# ESP32_Sensor.net
KiCad netlist of a schematic drawn in EAGLE
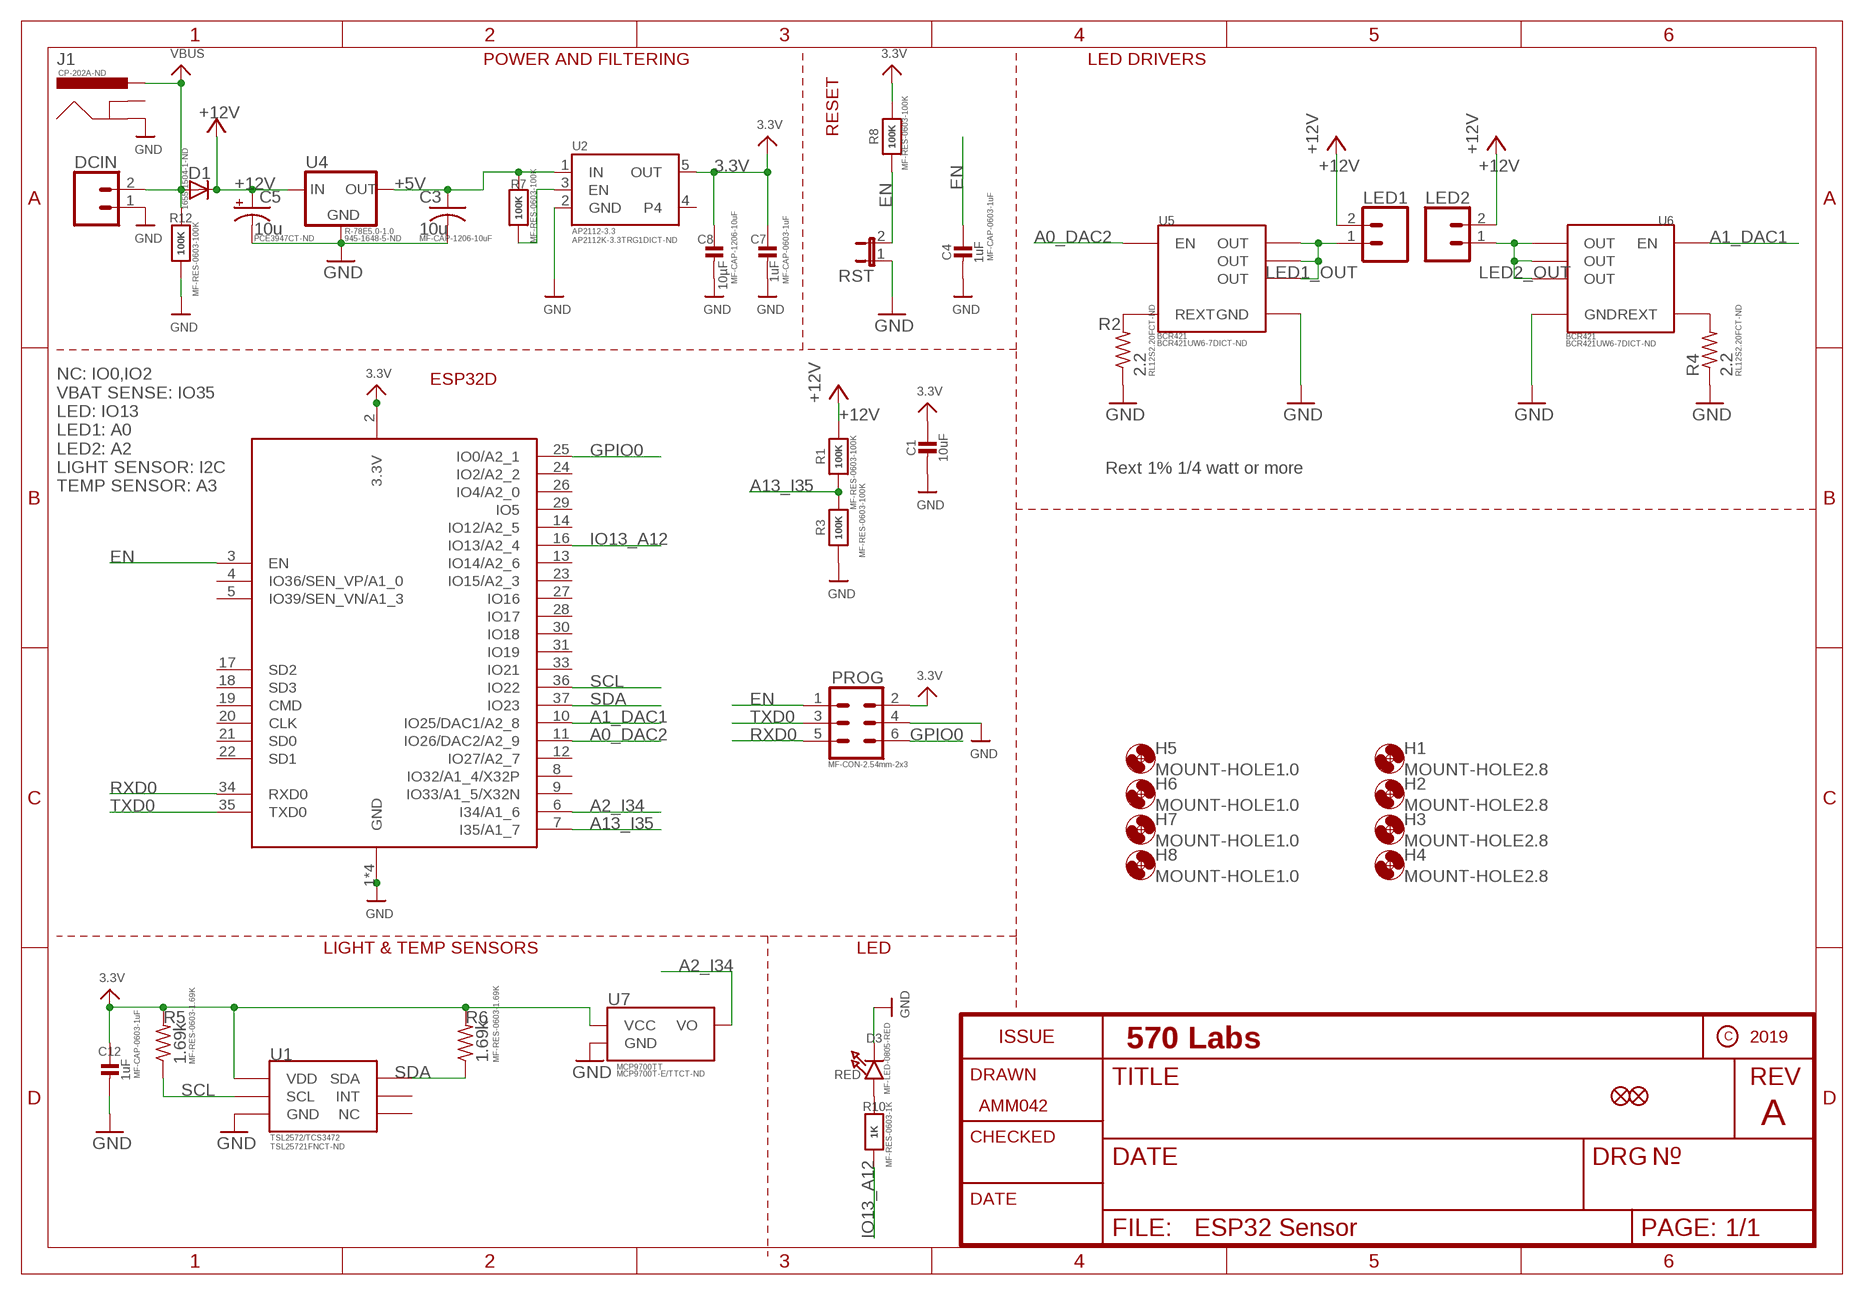
[diagram p0: schematic, sheet 1]

(export (version "E")
  (design (tool "Eeschema 10.0.6"))
  (components
    (comp (ref "C1")
      (value "10uF")
      (footprint "eagle-import:0805-NO")
      (libsource (lib "eagle-import") (part "CAP_CERAMIC0805-NOOUTLINE"))
    )
    (comp (ref "C3")
      (value "10u")
      (footprint "eagle-import:C1206")
      (fields (field (name "MF") "MF-CAP-1206-10uF"))
      (libsource (lib "eagle-import") (part "C-USC1206"))
    )
    (comp (ref "C4")
      (value "1uF")
      (footprint "eagle-import:0603-NO")
      (fields (field (name "MF") "MF-CAP-0603-1uF"))
      (libsource (lib "eagle-import") (part "CAP_CERAMIC0603_NO"))
    )
    (comp (ref "C5")
      (value "10u")
      (footprint "eagle-import:PANASONIC_C")
      (fields (field (name "DK") "PCE3947CT-ND"))
      (libsource (lib "eagle-import") (part "CPOL-USC"))
    )
    (comp (ref "C7")
      (value "1uF")
      (footprint "eagle-import:0603-NO")
      (fields (field (name "MF") "MF-CAP-0603-1uF"))
      (libsource (lib "eagle-import") (part "CAP_CERAMIC0603_NO"))
    )
    (comp (ref "C8")
      (value "10µF")
      (footprint "eagle-import:_1206")
      (fields (field (name "MF") "MF-CAP-1206-10uF"))
      (libsource (lib "eagle-import") (part "CAP_CERAMIC_1206"))
    )
    (comp (ref "C12")
      (value "1uF")
      (footprint "eagle-import:0603-NO")
      (fields (field (name "MF") "MF-CAP-0603-1uF"))
      (libsource (lib "eagle-import") (part "CAP_CERAMIC0603_NO"))
    )
    (comp (ref "D1")
      (value "DIODE-DO214AC")
      (footprint "eagle-import:DO214AC")
      (fields (field (name "DK") "1655-1504-1-ND"))
      (libsource (lib "eagle-import") (part "DIODE-DO214AC"))
    )
    (comp (ref "D3")
      (value "RED")
      (footprint "eagle-import:CHIPLED_0805_NOOUTLINE")
      (fields (field (name "MF") "MF-LED-0805-RED"))
      (libsource (lib "eagle-import") (part "LED0805_NOOUTLINE"))
    )
    (comp (ref "DCIN")
      (value "CONN_023.5MM")
      (footprint "eagle-import:SCREWTERMINAL-3.5MM-2")
      (libsource (lib "eagle-import") (part "CONN_023.5MM"))
    )
    (comp (ref "H1")
      (value "MOUNT-HOLE2.8")
      (footprint "eagle-import:2,8")
      (libsource (lib "eagle-import") (part "holes_237_MOUNT-HOLE2.8"))
    )
    (comp (ref "H2")
      (value "MOUNT-HOLE2.8")
      (footprint "eagle-import:2,8")
      (libsource (lib "eagle-import") (part "holes_237_MOUNT-HOLE2.8"))
    )
    (comp (ref "H3")
      (value "MOUNT-HOLE2.8")
      (footprint "eagle-import:2,8")
      (libsource (lib "eagle-import") (part "holes_237_MOUNT-HOLE2.8"))
    )
    (comp (ref "H4")
      (value "MOUNT-HOLE2.8")
      (footprint "eagle-import:2,8")
      (libsource (lib "eagle-import") (part "holes_237_MOUNT-HOLE2.8"))
    )
    (comp (ref "H5")
      (value "MOUNT-HOLE1.0")
      (footprint "eagle-import:1,0")
      (libsource (lib "eagle-import") (part "MOUNT-HOLE1.0"))
    )
    (comp (ref "H6")
      (value "MOUNT-HOLE1.0")
      (footprint "eagle-import:1,0")
      (libsource (lib "eagle-import") (part "MOUNT-HOLE1.0"))
    )
    (comp (ref "H7")
      (value "MOUNT-HOLE1.0")
      (footprint "eagle-import:1,0")
      (libsource (lib "eagle-import") (part "MOUNT-HOLE1.0"))
    )
    (comp (ref "H8")
      (value "MOUNT-HOLE1.0")
      (footprint "eagle-import:1,0")
      (libsource (lib "eagle-import") (part "MOUNT-HOLE1.0"))
    )
    (comp (ref "J1")
      (value "POWER_JACKPTH_LOCK")
      (footprint "eagle-import:POWER_JACK_PTH_LOCK")
      (libsource (lib "eagle-import") (part "POWER_JACKPTH_LOCK"))
    )
    (comp (ref "LED1")
      (value "CONN_023.5MM")
      (footprint "eagle-import:SCREWTERMINAL-3.5MM-2")
      (libsource (lib "eagle-import") (part "CONN_023.5MM"))
    )
    (comp (ref "LED2")
      (value "CONN_023.5MM")
      (footprint "eagle-import:SCREWTERMINAL-3.5MM-2")
      (libsource (lib "eagle-import") (part "CONN_023.5MM"))
    )
    (comp (ref "PROG")
      (value "CONN_03X2SHROUD")
      (footprint "eagle-import:2X3-SHROUDED")
      (fields (field (name "MF") "MF-CON-2.54mm-2x3"))
      (libsource (lib "eagle-import") (part "CONN_03X2SHROUD"))
    )
    (comp (ref "R1")
      (value "100K")
      (footprint "eagle-import:0603-NO")
      (fields (field (name "MF") "MF-RES-0603-100K"))
      (libsource (lib "eagle-import") (part "RESISTOR_0603_NOOUT"))
    )
    (comp (ref "R2")
      (value "2.2")
      (footprint "eagle-import:R0603")
      (fields (field (name "DK") "RL12S2.20FCT-ND"))
      (libsource (lib "eagle-import") (part "R-US_R0603"))
    )
    (comp (ref "R3")
      (value "100K")
      (footprint "eagle-import:0603-NO")
      (fields (field (name "MF") "MF-RES-0603-100K"))
      (libsource (lib "eagle-import") (part "RESISTOR_0603_NOOUT"))
    )
    (comp (ref "R4")
      (value "2.2")
      (footprint "eagle-import:R0603")
      (fields (field (name "DK") "RL12S2.20FCT-ND"))
      (libsource (lib "eagle-import") (part "R-US_R0603"))
    )
    (comp (ref "R5")
      (value "1.69k")
      (footprint "eagle-import:R0603")
      (fields (field (name "MF") "MF-RES-0603-1.69K"))
      (libsource (lib "eagle-import") (part "R-US_R0603"))
    )
    (comp (ref "R6")
      (value "1.69k")
      (footprint "eagle-import:R0603")
      (fields (field (name "MF") "MF-RES-0603-1.69K"))
      (libsource (lib "eagle-import") (part "R-US_R0603"))
    )
    (comp (ref "R7")
      (value "100K")
      (footprint "eagle-import:0603-NO")
      (fields (field (name "MF") "MF-RES-0603-100K"))
      (libsource (lib "eagle-import") (part "RESISTOR_0603_NOOUT"))
    )
    (comp (ref "R8")
      (value "100K")
      (footprint "eagle-import:0603-NO")
      (fields (field (name "MF") "MF-RES-0603-100K"))
      (libsource (lib "eagle-import") (part "RESISTOR_0603_NOOUT"))
    )
    (comp (ref "R10")
      (value "1K")
      (footprint "eagle-import:0603-NO")
      (fields (field (name "MF") "MF-RES-0603-1K"))
      (libsource (lib "eagle-import") (part "RESISTOR_0603_NOOUT"))
    )
    (comp (ref "R12")
      (value "100K")
      (footprint "eagle-import:0603-NO")
      (fields (field (name "MF") "MF-RES-0603-100K"))
      (libsource (lib "eagle-import") (part "RESISTOR_0603_NOOUT"))
    )
    (comp (ref "RST")
      (value "JP1E")
      (footprint "eagle-import:JP1")
      (libsource (lib "eagle-import") (part "JP1E"))
    )
    (comp (ref "U$34")
      (value "FIDUCIAL_1MM")
      (footprint "eagle-import:FIDUCIAL_1MM")
      (libsource (lib "eagle-import") (part "FIDUCIAL_1MM"))
    )
    (comp (ref "U$35")
      (value "FIDUCIAL_1MM")
      (footprint "eagle-import:FIDUCIAL_1MM")
      (libsource (lib "eagle-import") (part "FIDUCIAL_1MM"))
    )
    (comp (ref "U1")
      (value "TSL2572/TCS3472")
      (footprint "eagle-import:AMS_FN_6")
      (fields (field (name "DK") "TSL25721FNCT-ND"))
      (libsource (lib "eagle-import") (part "AMS_6FN_SENSOR"))
    )
    (comp (ref "U2")
      (value "AP2112-3.3")
      (footprint "eagle-import:SOT23-5")
      (fields (field (name "DK") "AP2112K-3.3TRG1DICT-ND"))
      (libsource (lib "eagle-import") (part "VREG_SOT23-5"))
    )
    (comp (ref "U3")
      (value "ESP32_WROOM32_SKINNY")
      (footprint "eagle-import:WROOM32_SKINNY")
      (libsource (lib "eagle-import") (part "ESP32_WROOM32_SKINNY"))
    )
    (comp (ref "U4")
      (value "R-78E5.0-1.0")
      (footprint "eagle-import:DC-DC_CONVERTER_78XX")
      (fields (field (name "DK") "945-1648-5-ND"))
      (libsource (lib "eagle-import") (part "R-78E5.0-1.0"))
    )
    (comp (ref "U5")
      (value "BCR421")
      (footprint "eagle-import:SOT26")
      (fields (field (name "DK") "BCR421UW6-7DICT-ND"))
      (libsource (lib "eagle-import") (part "BCR421"))
    )
    (comp (ref "U6")
      (value "BCR421")
      (footprint "eagle-import:SOT26")
      (fields (field (name "DK") "BCR421UW6-7DICT-ND"))
      (libsource (lib "eagle-import") (part "BCR421"))
    )
    (comp (ref "U7")
      (value "MCP9700TT")
      (footprint "eagle-import:SOT23-3")
      (fields (field (name "DK") "MCP9700T-E/TTCT-ND"))
      (libsource (lib "eagle-import") (part "MCP9700TT"))
    )
  )
  (nets
    (net (code "1") (name "+12V") (class "Default")
      (node (ref "C5") (pin "+") (pinfunction "+_+") (pintype "passive"))
      (node (ref "D1") (pin "C") (pinfunction "C_C") (pintype "passive"))
      (node (ref "LED1") (pin "2") (pinfunction "2_2") (pintype "passive"))
      (node (ref "LED2") (pin "2") (pinfunction "2_2") (pintype "passive"))
      (node (ref "R1") (pin "2") (pinfunction "2_2") (pintype "passive"))
      (node (ref "U4") (pin "VIN") (pinfunction "IN_VIN") (pintype "input"))
    )
    (net (code "2") (name "/+5V") (class "Default")
      (node (ref "C3") (pin "1") (pinfunction "1_1") (pintype "passive"))
      (node (ref "R7") (pin "2") (pinfunction "2_2") (pintype "passive"))
      (node (ref "U2") (pin "1") (pinfunction "IN_1") (pintype "power_in"))
      (node (ref "U4") (pin "VOUT") (pinfunction "OUT_VOUT") (pintype "passive"))
    )
    (net (code "3") (name "/A0_DAC2") (class "Default")
      (node (ref "U3") (pin "11") (pinfunction "IO26/DAC2/A2_9_11") (pintype "bidirectional"))
      (node (ref "U5") (pin "1") (pinfunction "EN_1") (pintype "bidirectional"))
    )
    (net (code "4") (name "/A1_DAC1") (class "Default")
      (node (ref "U3") (pin "10") (pinfunction "IO25/DAC1/A2_8_10") (pintype "bidirectional"))
      (node (ref "U6") (pin "1") (pinfunction "EN_1") (pintype "bidirectional"))
    )
    (net (code "5") (name "/A2_I34") (class "Default")
      (node (ref "U3") (pin "6") (pinfunction "I34/A1_6_6") (pintype "bidirectional"))
      (node (ref "U7") (pin "2") (pinfunction "VO_2") (pintype "bidirectional"))
    )
    (net (code "6") (name "/A13_I35") (class "Default")
      (node (ref "R1") (pin "1") (pinfunction "1_1") (pintype "passive"))
      (node (ref "R3") (pin "2") (pinfunction "2_2") (pintype "passive"))
      (node (ref "U3") (pin "7") (pinfunction "I35/A1_7_7") (pintype "bidirectional"))
    )
    (net (code "7") (name "/EN") (class "Default")
      (node (ref "C4") (pin "1") (pinfunction "1_1") (pintype "passive"))
      (node (ref "PROG") (pin "1") (pinfunction "1_1") (pintype "bidirectional"))
      (node (ref "R8") (pin "1") (pinfunction "1_1") (pintype "passive"))
      (node (ref "RST") (pin "2") (pinfunction "2_2") (pintype "passive"))
      (node (ref "U3") (pin "3") (pinfunction "EN_3") (pintype "input"))
    )
    (net (code "8") (name "/GPIO0") (class "Default")
      (node (ref "PROG") (pin "6") (pinfunction "6_6") (pintype "bidirectional"))
      (node (ref "U3") (pin "25") (pinfunction "IO0/A2_1_25") (pintype "bidirectional"))
    )
    (net (code "9") (name "/IO13_A12") (class "Default")
      (node (ref "R10") (pin "1") (pinfunction "1_1") (pintype "passive"))
      (node (ref "U3") (pin "16") (pinfunction "IO13/A2_4_16") (pintype "bidirectional"))
    )
    (net (code "10") (name "/LED1_OUT") (class "Default")
      (node (ref "LED1") (pin "1") (pinfunction "1_1") (pintype "passive"))
      (node (ref "U5") (pin "2") (pinfunction "OUT_2") (pintype "bidirectional"))
      (node (ref "U5") (pin "3") (pinfunction "OUT_3") (pintype "bidirectional"))
      (node (ref "U5") (pin "5") (pinfunction "OUT_5") (pintype "bidirectional"))
    )
    (net (code "11") (name "/LED2_OUT") (class "Default")
      (node (ref "LED2") (pin "1") (pinfunction "1_1") (pintype "passive"))
      (node (ref "U6") (pin "2") (pinfunction "OUT_2") (pintype "bidirectional"))
      (node (ref "U6") (pin "3") (pinfunction "OUT_3") (pintype "bidirectional"))
      (node (ref "U6") (pin "5") (pinfunction "OUT_5") (pintype "bidirectional"))
    )
    (net (code "12") (name "/RXD0") (class "Default")
      (node (ref "PROG") (pin "5") (pinfunction "5_5") (pintype "bidirectional"))
      (node (ref "U3") (pin "34") (pinfunction "RXD0_34") (pintype "input"))
    )
    (net (code "13") (name "/SCL") (class "Default")
      (node (ref "R5") (pin "1") (pinfunction "1_1") (pintype "passive"))
      (node (ref "U1") (pin "P$2") (pinfunction "SCL_P$2") (pintype "bidirectional"))
      (node (ref "U3") (pin "36") (pinfunction "IO22_36") (pintype "bidirectional"))
    )
    (net (code "14") (name "/SDA") (class "Default")
      (node (ref "R6") (pin "1") (pinfunction "1_1") (pintype "passive"))
      (node (ref "U1") (pin "P$6") (pinfunction "SDA_P$6") (pintype "bidirectional"))
      (node (ref "U3") (pin "37") (pinfunction "IO23_37") (pintype "bidirectional"))
    )
    (net (code "15") (name "/TXD0") (class "Default")
      (node (ref "PROG") (pin "3") (pinfunction "3_3") (pintype "bidirectional"))
      (node (ref "U3") (pin "35") (pinfunction "TXD0_35") (pintype "output"))
    )
    (net (code "16") (name "3.3V") (class "Default")
      (node (ref "C1") (pin "1") (pinfunction "1_1") (pintype "passive"))
      (node (ref "C12") (pin "1") (pinfunction "1_1") (pintype "passive"))
      (node (ref "C7") (pin "1") (pinfunction "1_1") (pintype "passive"))
      (node (ref "C8") (pin "1") (pinfunction "1_1") (pintype "passive"))
      (node (ref "PROG") (pin "2") (pinfunction "2_2") (pintype "bidirectional"))
      (node (ref "R5") (pin "2") (pinfunction "2_2") (pintype "passive"))
      (node (ref "R6") (pin "2") (pinfunction "2_2") (pintype "passive"))
      (node (ref "R8") (pin "2") (pinfunction "2_2") (pintype "passive"))
      (node (ref "U1") (pin "P$1") (pinfunction "VDD_P$1") (pintype "bidirectional"))
      (node (ref "U2") (pin "5") (pinfunction "OUT_5") (pintype "power_in"))
      (node (ref "U3") (pin "2") (pinfunction "3.3V_2") (pintype "passive"))
      (node (ref "U7") (pin "1") (pinfunction "VCC_1") (pintype "bidirectional"))
    )
    (net (code "17") (name "GND") (class "Default")
      (node (ref "C1") (pin "2") (pinfunction "2_2") (pintype "passive"))
      (node (ref "C12") (pin "2") (pinfunction "2_2") (pintype "passive"))
      (node (ref "C3") (pin "2") (pinfunction "2_2") (pintype "passive"))
      (node (ref "C4") (pin "2") (pinfunction "2_2") (pintype "passive"))
      (node (ref "C5") (pin "-") (pinfunction "-_-") (pintype "passive"))
      (node (ref "C7") (pin "2") (pinfunction "2_2") (pintype "passive"))
      (node (ref "C8") (pin "2") (pinfunction "2_2") (pintype "passive"))
      (node (ref "D3") (pin "C") (pinfunction "C_C") (pintype "passive"))
      (node (ref "DCIN") (pin "1") (pinfunction "1_1") (pintype "passive"))
      (node (ref "J1") (pin "GND") (pinfunction "GND_GND") (pintype "bidirectional"))
      (node (ref "PROG") (pin "4") (pinfunction "4_4") (pintype "bidirectional"))
      (node (ref "R12") (pin "1") (pinfunction "1_1") (pintype "passive"))
      (node (ref "R2") (pin "1") (pinfunction "1_1") (pintype "passive"))
      (node (ref "R3") (pin "1") (pinfunction "1_1") (pintype "passive"))
      (node (ref "R4") (pin "1") (pinfunction "1_1") (pintype "passive"))
      (node (ref "RST") (pin "1") (pinfunction "1_1") (pintype "passive"))
      (node (ref "U1") (pin "P$3") (pinfunction "GND_P$3") (pintype "bidirectional"))
      (node (ref "U2") (pin "2") (pinfunction "GND_2") (pintype "power_in"))
      (node (ref "U3") (pin "1") (pinfunction "GND_1") (pintype "passive"))
      (node (ref "U3") (pin "15") (pinfunction "GND_15") (pintype "passive"))
      (node (ref "U3") (pin "38") (pinfunction "GND_38") (pintype "passive"))
      (node (ref "U3") (pin "P$1") (pinfunction "GND_P$1") (pintype "passive"))
      (node (ref "U4") (pin "GND") (pinfunction "GND_GND") (pintype "input"))
      (node (ref "U5") (pin "4") (pinfunction "GND_4") (pintype "bidirectional"))
      (node (ref "U6") (pin "4") (pinfunction "GND_4") (pintype "bidirectional"))
      (node (ref "U7") (pin "3") (pinfunction "GND_3") (pintype "bidirectional"))
    )
    (net (code "18") (name "Net-(D3-PadA)") (class "Default")
      (node (ref "D3") (pin "A") (pinfunction "A_A") (pintype "passive"))
      (node (ref "R10") (pin "2") (pinfunction "2_2") (pintype "passive"))
    )
    (net (code "19") (name "Net-(U2-EN)") (class "Default")
      (node (ref "R7") (pin "1") (pinfunction "1_1") (pintype "passive"))
      (node (ref "U2") (pin "3") (pinfunction "EN_3") (pintype "input"))
    )
    (net (code "20") (name "Net-(U5-REXT)") (class "Default")
      (node (ref "R2") (pin "2") (pinfunction "2_2") (pintype "passive"))
      (node (ref "U5") (pin "6") (pinfunction "REXT_6") (pintype "bidirectional"))
    )
    (net (code "21") (name "Net-(U6-REXT)") (class "Default")
      (node (ref "R4") (pin "2") (pinfunction "2_2") (pintype "passive"))
      (node (ref "U6") (pin "6") (pinfunction "REXT_6") (pintype "bidirectional"))
    )
    (net (code "22") (name "VBUS") (class "Default")
      (node (ref "D1") (pin "A") (pinfunction "A_A") (pintype "passive"))
      (node (ref "DCIN") (pin "2") (pinfunction "2_2") (pintype "passive"))
      (node (ref "J1") (pin "PWR") (pinfunction "PWR_PWR") (pintype "bidirectional"))
      (node (ref "R12") (pin "2") (pinfunction "2_2") (pintype "passive"))
    )
    (net (code "23") (name "unconnected-(J1-PadGNDBREAK)") (class "Default")
      (node (ref "J1") (pin "GNDBREAK") (pinfunction "GNDBREAK_GNDBREAK") (pintype "bidirectional"))
    )
    (net (code "24") (name "unconnected-(U1-INT-PadP$5)") (class "Default")
      (node (ref "U1") (pin "P$5") (pinfunction "INT_P$5") (pintype "bidirectional"))
    )
    (net (code "25") (name "unconnected-(U1-NC-PadP$4)") (class "Default")
      (node (ref "U1") (pin "P$4") (pinfunction "NC_P$4") (pintype "bidirectional"))
    )
    (net (code "26") (name "unconnected-(U2-P4-Pad4)") (class "Default")
      (node (ref "U2") (pin "4") (pinfunction "P4_4") (pintype "bidirectional"))
    )
    (net (code "27") (name "unconnected-(U3-CLK-Pad20)") (class "Default")
      (node (ref "U3") (pin "20") (pinfunction "CLK_20") (pintype "bidirectional"))
    )
    (net (code "28") (name "unconnected-(U3-CMD-Pad19)") (class "Default")
      (node (ref "U3") (pin "19") (pinfunction "CMD_19") (pintype "bidirectional"))
    )
    (net (code "29") (name "unconnected-(U3-IO2{slash}A2_2-Pad24)") (class "Default")
      (node (ref "U3") (pin "24") (pinfunction "IO2/A2_2_24") (pintype "bidirectional"))
    )
    (net (code "30") (name "unconnected-(U3-IO4{slash}A2_0-Pad26)") (class "Default")
      (node (ref "U3") (pin "26") (pinfunction "IO4/A2_0_26") (pintype "bidirectional"))
    )
    (net (code "31") (name "unconnected-(U3-IO5-Pad29)") (class "Default")
      (node (ref "U3") (pin "29") (pinfunction "IO5_29") (pintype "bidirectional"))
    )
    (net (code "32") (name "unconnected-(U3-IO12{slash}A2_5-Pad14)") (class "Default")
      (node (ref "U3") (pin "14") (pinfunction "IO12/A2_5_14") (pintype "bidirectional"))
    )
    (net (code "33") (name "unconnected-(U3-IO14{slash}A2_6-Pad13)") (class "Default")
      (node (ref "U3") (pin "13") (pinfunction "IO14/A2_6_13") (pintype "bidirectional"))
    )
    (net (code "34") (name "unconnected-(U3-IO15{slash}A2_3-Pad23)") (class "Default")
      (node (ref "U3") (pin "23") (pinfunction "IO15/A2_3_23") (pintype "bidirectional"))
    )
    (net (code "35") (name "unconnected-(U3-IO16-Pad27)") (class "Default")
      (node (ref "U3") (pin "27") (pinfunction "IO16_27") (pintype "bidirectional"))
    )
    (net (code "36") (name "unconnected-(U3-IO17-Pad28)") (class "Default")
      (node (ref "U3") (pin "28") (pinfunction "IO17_28") (pintype "bidirectional"))
    )
    (net (code "37") (name "unconnected-(U3-IO18-Pad30)") (class "Default")
      (node (ref "U3") (pin "30") (pinfunction "IO18_30") (pintype "bidirectional"))
    )
    (net (code "38") (name "unconnected-(U3-IO19-Pad31)") (class "Default")
      (node (ref "U3") (pin "31") (pinfunction "IO19_31") (pintype "bidirectional"))
    )
    (net (code "39") (name "unconnected-(U3-IO21-Pad33)") (class "Default")
      (node (ref "U3") (pin "33") (pinfunction "IO21_33") (pintype "bidirectional"))
    )
    (net (code "40") (name "unconnected-(U3-IO27{slash}A2_7-Pad12)") (class "Default")
      (node (ref "U3") (pin "12") (pinfunction "IO27/A2_7_12") (pintype "bidirectional"))
    )
    (net (code "41") (name "unconnected-(U3-IO32{slash}A1_4{slash}X32P-Pad8)") (class "Default")
      (node (ref "U3") (pin "8") (pinfunction "IO32/A1_4/X32P_8") (pintype "bidirectional"))
    )
    (net (code "42") (name "unconnected-(U3-IO33{slash}A1_5{slash}X32N-Pad9)") (class "Default")
      (node (ref "U3") (pin "9") (pinfunction "IO33/A1_5/X32N_9") (pintype "bidirectional"))
    )
    (net (code "43") (name "unconnected-(U3-IO36{slash}SEN_VP{slash}A1_0-Pad4)") (class "Default")
      (node (ref "U3") (pin "4") (pinfunction "IO36/SEN_VP/A1_0_4") (pintype "passive"))
    )
    (net (code "44") (name "unconnected-(U3-IO39{slash}SEN_VN{slash}A1_3-Pad5)") (class "Default")
      (node (ref "U3") (pin "5") (pinfunction "IO39/SEN_VN/A1_3_5") (pintype "passive"))
    )
    (net (code "45") (name "unconnected-(U3-SD0-Pad21)") (class "Default")
      (node (ref "U3") (pin "21") (pinfunction "SD0_21") (pintype "bidirectional"))
    )
    (net (code "46") (name "unconnected-(U3-SD1-Pad22)") (class "Default")
      (node (ref "U3") (pin "22") (pinfunction "SD1_22") (pintype "bidirectional"))
    )
    (net (code "47") (name "unconnected-(U3-SD2-Pad17)") (class "Default")
      (node (ref "U3") (pin "17") (pinfunction "SD2_17") (pintype "bidirectional"))
    )
    (net (code "48") (name "unconnected-(U3-SD3-Pad18)") (class "Default")
      (node (ref "U3") (pin "18") (pinfunction "SD3_18") (pintype "bidirectional"))
    )
  )
)
